# schematic.net
KiCad netlist of a schematic drawn in EAGLE
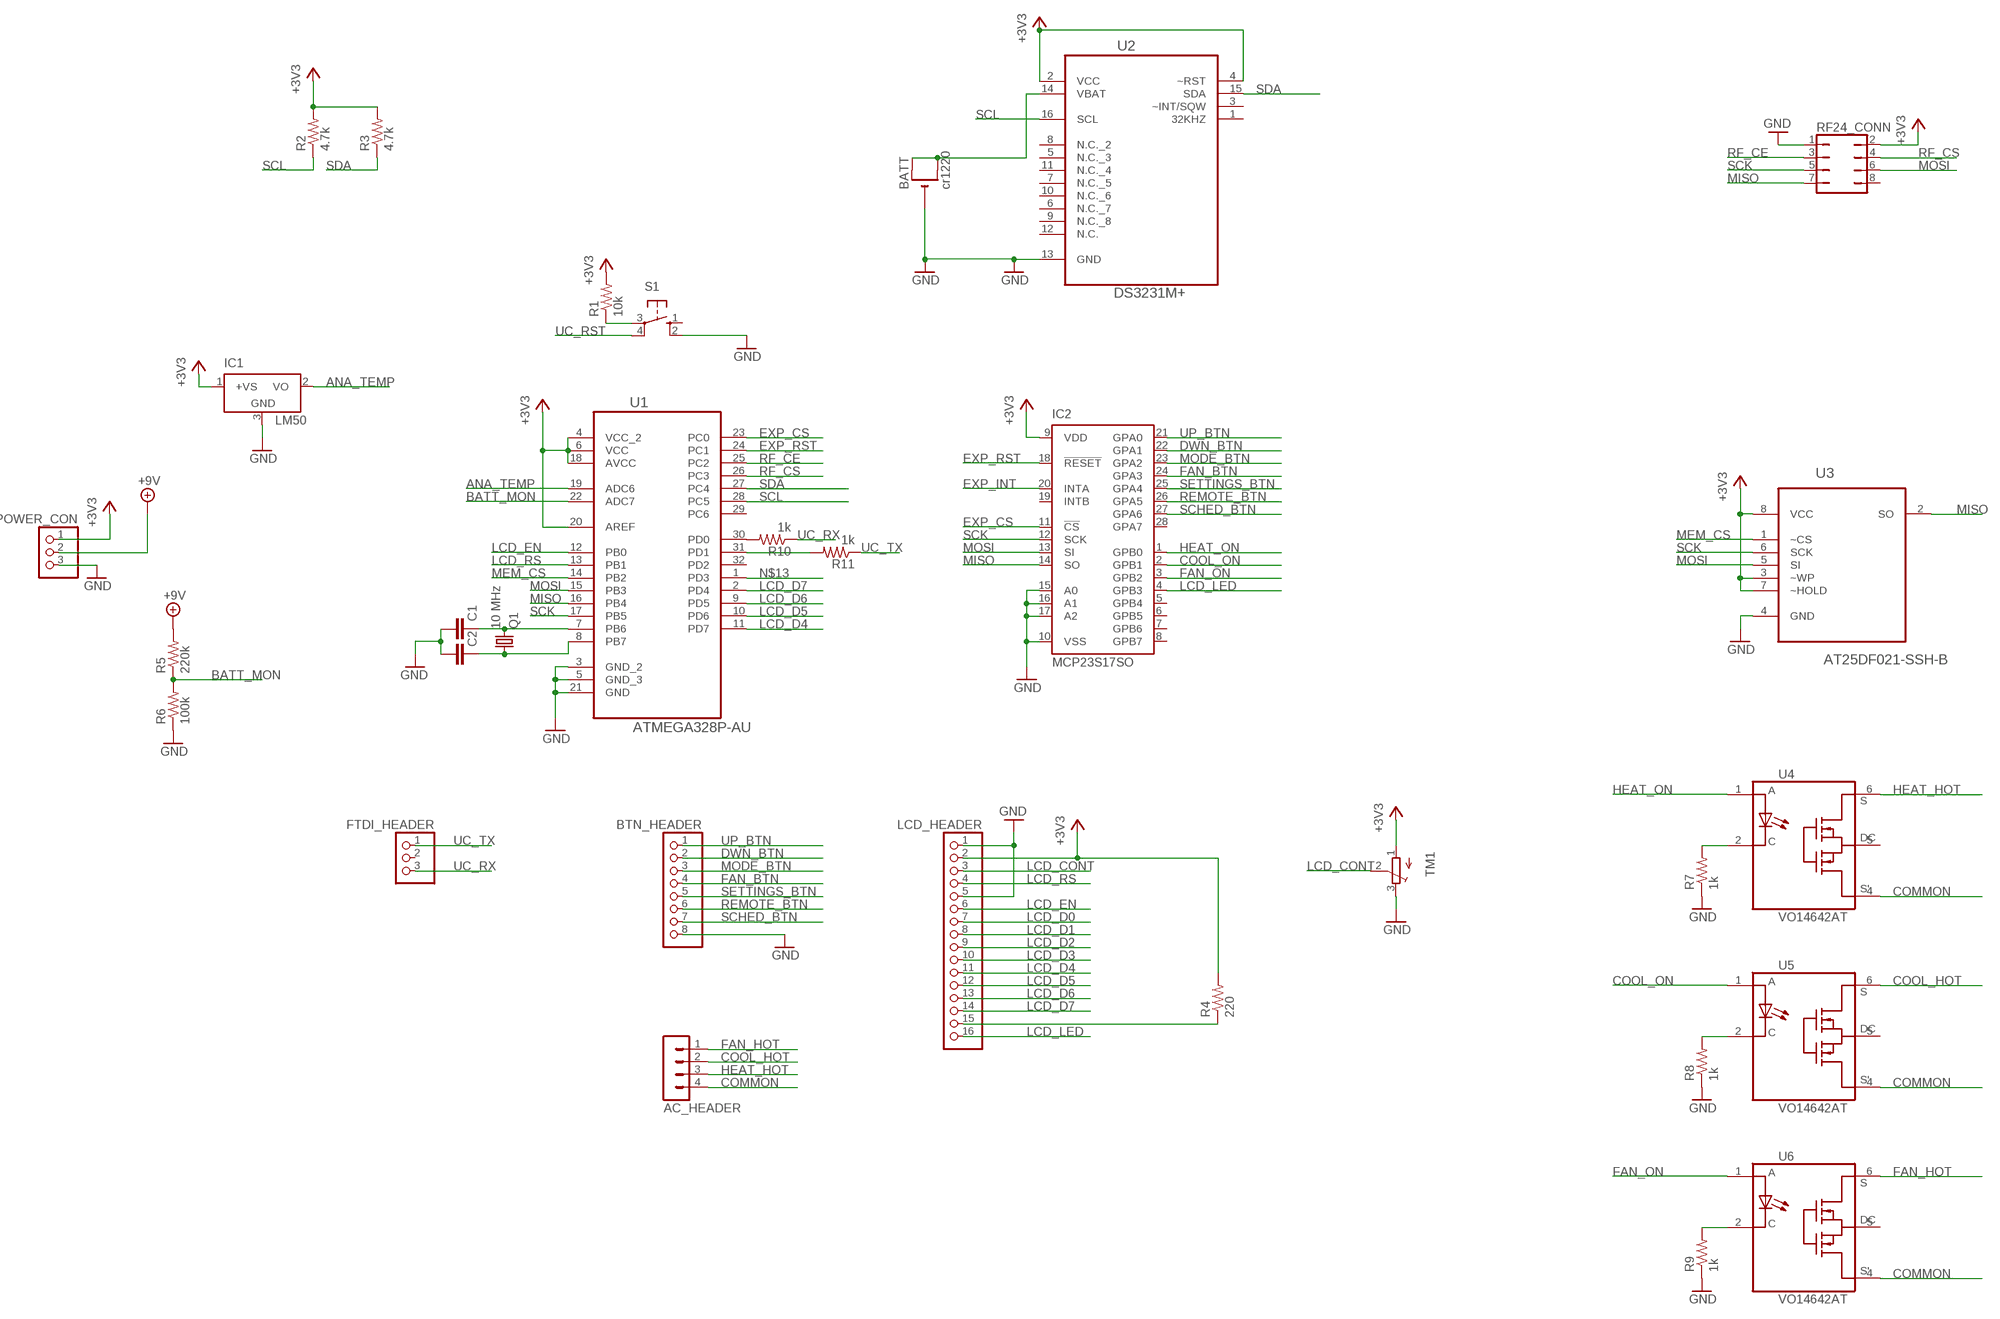
[diagram p0: schematic, sheet 1]

(export (version "E")
  (design (tool "Eeschema 10.0.6"))
  (components
    (comp (ref "AC_HEADER")
      (value "MA04-1")
      (footprint "eagle-import:MA04-1")
      (libsource (lib "eagle-import") (part "MA04-1"))
    )
    (comp (ref "BATT")
      (value "cr1220")
      (footprint "eagle-import:CR1220-SMD")
      (libsource (lib "eagle-import") (part "CR1220SMT"))
    )
    (comp (ref "BTN_HEADER")
      (value "PINHD-1X8BIG")
      (footprint "eagle-import:1X08-BIG")
      (libsource (lib "eagle-import") (part "PINHD-1X8BIG"))
    )
    (comp (ref "C1")
      (value "C-EUC0402")
      (footprint "eagle-import:C0402")
      (libsource (lib "eagle-import") (part "C-EUC0402"))
    )
    (comp (ref "C2")
      (value "C-EUC0402")
      (footprint "eagle-import:C0402")
      (libsource (lib "eagle-import") (part "C-EUC0402"))
    )
    (comp (ref "FTDI_HEADER")
      (value "PINHD-1X3")
      (footprint "eagle-import:1X03")
      (libsource (lib "eagle-import") (part "PINHD-1X3"))
    )
    (comp (ref "IC1")
      (value "LM50")
      (footprint "eagle-import:SOT23")
      (libsource (lib "eagle-import") (part "LM50"))
    )
    (comp (ref "IC2")
      (value "MCP23S17SO")
      (footprint "eagle-import:SO28W")
      (fields (field (name "MF") "MICROCHIP") (field (name "MPN") "MCP23S17-E/SO"))
      (libsource (lib "eagle-import") (part "MCP23S17SO"))
    )
    (comp (ref "LCD_HEADER")
      (value "PINHD-1X16")
      (footprint "eagle-import:1X16")
      (libsource (lib "eagle-import") (part "PINHD-1X16"))
    )
    (comp (ref "POWER_CON")
      (value "PINHD-1X3")
      (footprint "eagle-import:1X03")
      (libsource (lib "eagle-import") (part "PINHD-1X3"))
    )
    (comp (ref "Q1")
      (value "10 MHz")
      (footprint "eagle-import:FC-12M")
      (libsource (lib "eagle-import") (part "FC-12M"))
    )
    (comp (ref "R1")
      (value "10k")
      (footprint "eagle-import:R0402")
      (libsource (lib "eagle-import") (part "R-US_R0402"))
    )
    (comp (ref "R2")
      (value "4.7k")
      (footprint "eagle-import:R0402")
      (libsource (lib "eagle-import") (part "R-US_R0402"))
    )
    (comp (ref "R3")
      (value "4.7k")
      (footprint "eagle-import:R0402")
      (libsource (lib "eagle-import") (part "R-US_R0402"))
    )
    (comp (ref "R4")
      (value "220")
      (footprint "eagle-import:R0402")
      (libsource (lib "eagle-import") (part "R-US_R0402"))
    )
    (comp (ref "R5")
      (value "220k")
      (footprint "eagle-import:R0402")
      (libsource (lib "eagle-import") (part "R-US_R0402"))
    )
    (comp (ref "R6")
      (value "100k")
      (footprint "eagle-import:R0402")
      (libsource (lib "eagle-import") (part "R-US_R0402"))
    )
    (comp (ref "R7")
      (value "1k")
      (footprint "eagle-import:R0402")
      (libsource (lib "eagle-import") (part "R-US_R0402"))
    )
    (comp (ref "R8")
      (value "1k")
      (footprint "eagle-import:R0402")
      (libsource (lib "eagle-import") (part "R-US_R0402"))
    )
    (comp (ref "R9")
      (value "1k")
      (footprint "eagle-import:R0402")
      (libsource (lib "eagle-import") (part "R-US_R0402"))
    )
    (comp (ref "R10")
      (value "1k")
      (footprint "eagle-import:R0402")
      (libsource (lib "eagle-import") (part "R-US_R0402"))
    )
    (comp (ref "R11")
      (value "1k")
      (footprint "eagle-import:R0402")
      (libsource (lib "eagle-import") (part "R-US_R0402"))
    )
    (comp (ref "RF24_CONN")
      (value "JP4Q")
      (footprint "eagle-import:JP4Q")
      (libsource (lib "eagle-import") (part "JP4Q"))
    )
    (comp (ref "S1")
      (value "10-XX")
      (footprint "eagle-import:B3F-10XX")
      (fields (field (name "MPN") "B3F-1000"))
      (libsource (lib "eagle-import") (part "10-XX"))
    )
    (comp (ref "TM1")
      (value "TRIMPOTTC33X")
      (footprint "eagle-import:TC33X")
      (libsource (lib "eagle-import") (part "TRIMPOTTC33X"))
    )
    (comp (ref "U1")
      (value "ATMEGA328P-AU")
      (footprint "eagle-import:QFP80P900X900X120-32N")
      (libsource (lib "eagle-import") (part "ATMEGA328P-AU"))
    )
    (comp (ref "U2")
      (value "DS3231M+")
      (footprint "eagle-import:SOIC127P1032X265-16N")
      (libsource (lib "eagle-import") (part "DS3231M+"))
    )
    (comp (ref "U3")
      (value "AT25DF021-SSH-B")
      (footprint "eagle-import:SOIC127P600X175-8N")
      (libsource (lib "eagle-import") (part "AT25DF021-SSH-B"))
    )
    (comp (ref "U4")
      (value "VO14642AT")
      (footprint "eagle-import:DIP762W50P254L730H410Q6")
      (fields (field (name "DIGI-KEY_PART_NUMBER") "VO14642AT-ND") (field (name "MF") "Vishay"))
      (libsource (lib "eagle-import") (part "VO14642AT"))
    )
    (comp (ref "U5")
      (value "VO14642AT")
      (footprint "eagle-import:DIP762W50P254L730H410Q6")
      (fields (field (name "DIGI-KEY_PART_NUMBER") "VO14642AT-ND") (field (name "MF") "Vishay"))
      (libsource (lib "eagle-import") (part "VO14642AT"))
    )
    (comp (ref "U6")
      (value "VO14642AT")
      (footprint "eagle-import:DIP762W50P254L730H410Q6")
      (fields (field (name "DIGI-KEY_PART_NUMBER") "VO14642AT-ND") (field (name "MF") "Vishay"))
      (libsource (lib "eagle-import") (part "VO14642AT"))
    )
  )
  (nets
    (net (code "1") (name "+3V3") (class "Default")
      (node (ref "IC1") (pin "1") (pinfunction "+VS_1") (pintype "input"))
      (node (ref "IC2") (pin "9") (pinfunction "VDD_9") (pintype "power_in"))
      (node (ref "LCD_HEADER") (pin "2") (pinfunction "2_2") (pintype "passive"))
      (node (ref "POWER_CON") (pin "1") (pinfunction "1_1") (pintype "passive"))
      (node (ref "R1") (pin "2") (pinfunction "2_2") (pintype "passive"))
      (node (ref "R2") (pin "2") (pinfunction "2_2") (pintype "passive"))
      (node (ref "R3") (pin "2") (pinfunction "2_2") (pintype "passive"))
      (node (ref "R4") (pin "2") (pinfunction "2_2") (pintype "passive"))
      (node (ref "RF24_CONN") (pin "2") (pinfunction "2_2") (pintype "passive"))
      (node (ref "TM1") (pin "1") (pinfunction "A_1") (pintype "passive"))
      (node (ref "U1") (pin "18") (pinfunction "AVCC_18") (pintype "power_in"))
      (node (ref "U1") (pin "20") (pinfunction "AREF_20") (pintype "input"))
      (node (ref "U1") (pin "4") (pinfunction "VCC_2_4") (pintype "power_in"))
      (node (ref "U1") (pin "6") (pinfunction "VCC_6") (pintype "power_in"))
      (node (ref "U2") (pin "2") (pinfunction "VCC_2") (pintype "power_in"))
      (node (ref "U2") (pin "4") (pinfunction "~{RST}_4") (pintype "bidirectional"))
      (node (ref "U3") (pin "3") (pinfunction "~{WP}_3") (pintype "input"))
      (node (ref "U3") (pin "7") (pinfunction "~{HOLD}_7") (pintype "input"))
      (node (ref "U3") (pin "8") (pinfunction "VCC_8") (pintype "power_in"))
    )
    (net (code "2") (name "+9V") (class "Default")
      (node (ref "POWER_CON") (pin "2") (pinfunction "2_2") (pintype "passive"))
      (node (ref "R5") (pin "2") (pinfunction "2_2") (pintype "passive"))
    )
    (net (code "3") (name "/ANA_TEMP") (class "Default")
      (node (ref "IC1") (pin "2") (pinfunction "VO_2") (pintype "input"))
      (node (ref "U1") (pin "19") (pinfunction "ADC6_19") (pintype "input"))
    )
    (net (code "4") (name "/BATT_MON") (class "Default")
      (node (ref "R5") (pin "1") (pinfunction "1_1") (pintype "passive"))
      (node (ref "R6") (pin "2") (pinfunction "2_2") (pintype "passive"))
      (node (ref "U1") (pin "22") (pinfunction "ADC7_22") (pintype "input"))
    )
    (net (code "5") (name "/COMMON") (class "Default")
      (node (ref "AC_HEADER") (pin "4") (pinfunction "4_4") (pintype "passive"))
      (node (ref "U4") (pin "4") (pinfunction "S'_4") (pintype "passive"))
      (node (ref "U5") (pin "4") (pinfunction "S'_4") (pintype "passive"))
      (node (ref "U6") (pin "4") (pinfunction "S'_4") (pintype "passive"))
    )
    (net (code "6") (name "/COOL_HOT") (class "Default")
      (node (ref "AC_HEADER") (pin "2") (pinfunction "2_2") (pintype "passive"))
      (node (ref "U5") (pin "6") (pinfunction "S_6") (pintype "passive"))
    )
    (net (code "7") (name "/COOL_ON") (class "Default")
      (node (ref "IC2") (pin "2") (pinfunction "GPB1_2") (pintype "bidirectional"))
      (node (ref "U5") (pin "1") (pinfunction "A_1") (pintype "passive"))
    )
    (net (code "8") (name "/DWN_BTN") (class "Default")
      (node (ref "BTN_HEADER") (pin "2") (pinfunction "2_2") (pintype "passive"))
      (node (ref "IC2") (pin "22") (pinfunction "GPA1_22") (pintype "bidirectional"))
    )
    (net (code "9") (name "/EXP_CS") (class "Default")
      (node (ref "IC2") (pin "11") (pinfunction "~{CS}_11") (pintype "input"))
      (node (ref "U1") (pin "23") (pinfunction "PC0_23") (pintype "bidirectional"))
    )
    (net (code "10") (name "/EXP_INT") (class "Default")
      (node (ref "IC2") (pin "20") (pinfunction "INTA_20") (pintype "output"))
    )
    (net (code "11") (name "/EXP_RST") (class "Default")
      (node (ref "IC2") (pin "18") (pinfunction "~{RESET}_18") (pintype "input"))
      (node (ref "U1") (pin "24") (pinfunction "PC1_24") (pintype "bidirectional"))
    )
    (net (code "12") (name "/FAN_BTN") (class "Default")
      (node (ref "BTN_HEADER") (pin "4") (pinfunction "4_4") (pintype "passive"))
      (node (ref "IC2") (pin "24") (pinfunction "GPA3_24") (pintype "bidirectional"))
    )
    (net (code "13") (name "/FAN_HOT") (class "Default")
      (node (ref "AC_HEADER") (pin "1") (pinfunction "1_1") (pintype "passive"))
      (node (ref "U6") (pin "6") (pinfunction "S_6") (pintype "passive"))
    )
    (net (code "14") (name "/FAN_ON") (class "Default")
      (node (ref "IC2") (pin "3") (pinfunction "GPB2_3") (pintype "bidirectional"))
      (node (ref "U6") (pin "1") (pinfunction "A_1") (pintype "passive"))
    )
    (net (code "15") (name "/HEAT_HOT") (class "Default")
      (node (ref "AC_HEADER") (pin "3") (pinfunction "3_3") (pintype "passive"))
      (node (ref "U4") (pin "6") (pinfunction "S_6") (pintype "passive"))
    )
    (net (code "16") (name "/HEAT_ON") (class "Default")
      (node (ref "IC2") (pin "1") (pinfunction "GPB0_1") (pintype "bidirectional"))
      (node (ref "U4") (pin "1") (pinfunction "A_1") (pintype "passive"))
    )
    (net (code "17") (name "/LCD_CONT") (class "Default")
      (node (ref "LCD_HEADER") (pin "3") (pinfunction "3_3") (pintype "passive"))
      (node (ref "TM1") (pin "2") (pinfunction "S_2") (pintype "passive"))
    )
    (net (code "18") (name "/LCD_D0") (class "Default")
      (node (ref "LCD_HEADER") (pin "7") (pinfunction "7_7") (pintype "passive"))
    )
    (net (code "19") (name "/LCD_D1") (class "Default")
      (node (ref "LCD_HEADER") (pin "8") (pinfunction "8_8") (pintype "passive"))
    )
    (net (code "20") (name "/LCD_D2") (class "Default")
      (node (ref "LCD_HEADER") (pin "9") (pinfunction "9_9") (pintype "passive"))
    )
    (net (code "21") (name "/LCD_D3") (class "Default")
      (node (ref "LCD_HEADER") (pin "10") (pinfunction "10_10") (pintype "passive"))
    )
    (net (code "22") (name "/LCD_D4") (class "Default")
      (node (ref "LCD_HEADER") (pin "11") (pinfunction "11_11") (pintype "passive"))
      (node (ref "U1") (pin "11") (pinfunction "PD7_11") (pintype "bidirectional"))
    )
    (net (code "23") (name "/LCD_D5") (class "Default")
      (node (ref "LCD_HEADER") (pin "12") (pinfunction "12_12") (pintype "passive"))
      (node (ref "U1") (pin "10") (pinfunction "PD6_10") (pintype "bidirectional"))
    )
    (net (code "24") (name "/LCD_D6") (class "Default")
      (node (ref "LCD_HEADER") (pin "13") (pinfunction "13_13") (pintype "passive"))
      (node (ref "U1") (pin "9") (pinfunction "PD5_9") (pintype "bidirectional"))
    )
    (net (code "25") (name "/LCD_D7") (class "Default")
      (node (ref "LCD_HEADER") (pin "14") (pinfunction "14_14") (pintype "passive"))
      (node (ref "U1") (pin "2") (pinfunction "PD4_2") (pintype "bidirectional"))
    )
    (net (code "26") (name "/LCD_EN") (class "Default")
      (node (ref "LCD_HEADER") (pin "6") (pinfunction "6_6") (pintype "passive"))
      (node (ref "U1") (pin "12") (pinfunction "PB0_12") (pintype "bidirectional"))
    )
    (net (code "27") (name "/LCD_LED") (class "Default")
      (node (ref "IC2") (pin "4") (pinfunction "GPB3_4") (pintype "bidirectional"))
      (node (ref "LCD_HEADER") (pin "16") (pinfunction "16_16") (pintype "passive"))
    )
    (net (code "28") (name "/LCD_RS") (class "Default")
      (node (ref "LCD_HEADER") (pin "4") (pinfunction "4_4") (pintype "passive"))
      (node (ref "U1") (pin "13") (pinfunction "PB1_13") (pintype "bidirectional"))
    )
    (net (code "29") (name "/MEM_CS") (class "Default")
      (node (ref "U1") (pin "14") (pinfunction "PB2_14") (pintype "bidirectional"))
      (node (ref "U3") (pin "1") (pinfunction "~{CS}_1") (pintype "input"))
    )
    (net (code "30") (name "/MISO") (class "Default")
      (node (ref "IC2") (pin "14") (pinfunction "SO_14") (pintype "output"))
      (node (ref "RF24_CONN") (pin "7") (pinfunction "7_7") (pintype "passive"))
      (node (ref "U1") (pin "16") (pinfunction "PB4_16") (pintype "bidirectional"))
      (node (ref "U3") (pin "2") (pinfunction "SO_2") (pintype "output"))
    )
    (net (code "31") (name "/MODE_BTN") (class "Default")
      (node (ref "BTN_HEADER") (pin "3") (pinfunction "3_3") (pintype "passive"))
      (node (ref "IC2") (pin "23") (pinfunction "GPA2_23") (pintype "bidirectional"))
    )
    (net (code "32") (name "/MOSI") (class "Default")
      (node (ref "IC2") (pin "13") (pinfunction "SI_13") (pintype "input"))
      (node (ref "RF24_CONN") (pin "6") (pinfunction "6_6") (pintype "passive"))
      (node (ref "U1") (pin "15") (pinfunction "PB3_15") (pintype "bidirectional"))
      (node (ref "U3") (pin "5") (pinfunction "SI_5") (pintype "input"))
    )
    (net (code "33") (name "/N$13") (class "Default")
      (node (ref "U1") (pin "1") (pinfunction "PD3_1") (pintype "bidirectional"))
    )
    (net (code "34") (name "/REMOTE_BTN") (class "Default")
      (node (ref "BTN_HEADER") (pin "6") (pinfunction "6_6") (pintype "passive"))
      (node (ref "IC2") (pin "26") (pinfunction "GPA5_26") (pintype "bidirectional"))
    )
    (net (code "35") (name "/RF_CE") (class "Default")
      (node (ref "RF24_CONN") (pin "3") (pinfunction "3_3") (pintype "passive"))
      (node (ref "U1") (pin "25") (pinfunction "PC2_25") (pintype "bidirectional"))
    )
    (net (code "36") (name "/RF_CS") (class "Default")
      (node (ref "RF24_CONN") (pin "4") (pinfunction "4_4") (pintype "passive"))
      (node (ref "U1") (pin "26") (pinfunction "PC3_26") (pintype "bidirectional"))
    )
    (net (code "37") (name "/SCHED_BTN") (class "Default")
      (node (ref "BTN_HEADER") (pin "7") (pinfunction "7_7") (pintype "passive"))
      (node (ref "IC2") (pin "27") (pinfunction "GPA6_27") (pintype "bidirectional"))
    )
    (net (code "38") (name "/SCK") (class "Default")
      (node (ref "IC2") (pin "12") (pinfunction "SCK_12") (pintype "input"))
      (node (ref "RF24_CONN") (pin "5") (pinfunction "5_5") (pintype "passive"))
      (node (ref "U1") (pin "17") (pinfunction "PB5_17") (pintype "bidirectional"))
      (node (ref "U3") (pin "6") (pinfunction "SCK_6") (pintype "input"))
    )
    (net (code "39") (name "/SCL") (class "Default")
      (node (ref "R2") (pin "1") (pinfunction "1_1") (pintype "passive"))
      (node (ref "U1") (pin "28") (pinfunction "PC5_28") (pintype "bidirectional"))
      (node (ref "U2") (pin "16") (pinfunction "SCL_16") (pintype "input"))
    )
    (net (code "40") (name "/SDA") (class "Default")
      (node (ref "R3") (pin "1") (pinfunction "1_1") (pintype "passive"))
      (node (ref "U1") (pin "27") (pinfunction "PC4_27") (pintype "bidirectional"))
      (node (ref "U2") (pin "15") (pinfunction "SDA_15") (pintype "bidirectional"))
    )
    (net (code "41") (name "/SETTINGS_BTN") (class "Default")
      (node (ref "BTN_HEADER") (pin "5") (pinfunction "5_5") (pintype "passive"))
      (node (ref "IC2") (pin "25") (pinfunction "GPA4_25") (pintype "bidirectional"))
    )
    (net (code "42") (name "/UC_RST") (class "Default")
      (node (ref "S1") (pin "4") (pinfunction "P1_4") (pintype "passive"))
    )
    (net (code "43") (name "/UC_RX") (class "Default")
      (node (ref "FTDI_HEADER") (pin "3") (pinfunction "3_3") (pintype "passive"))
      (node (ref "R10") (pin "1") (pinfunction "1_1") (pintype "passive"))
    )
    (net (code "44") (name "/UC_TX") (class "Default")
      (node (ref "FTDI_HEADER") (pin "1") (pinfunction "1_1") (pintype "passive"))
      (node (ref "R11") (pin "1") (pinfunction "1_1") (pintype "passive"))
    )
    (net (code "45") (name "/UP_BTN") (class "Default")
      (node (ref "BTN_HEADER") (pin "1") (pinfunction "1_1") (pintype "passive"))
      (node (ref "IC2") (pin "21") (pinfunction "GPA0_21") (pintype "bidirectional"))
    )
    (net (code "46") (name "GND") (class "Default")
      (node (ref "BATT") (pin "-") (pinfunction "-_-") (pintype "passive"))
      (node (ref "BTN_HEADER") (pin "8") (pinfunction "8_8") (pintype "passive"))
      (node (ref "C1") (pin "2") (pinfunction "2_2") (pintype "passive"))
      (node (ref "C2") (pin "2") (pinfunction "2_2") (pintype "passive"))
      (node (ref "IC1") (pin "3") (pinfunction "GND_3") (pintype "power_in"))
      (node (ref "IC2") (pin "10") (pinfunction "VSS_10") (pintype "power_in"))
      (node (ref "IC2") (pin "15") (pinfunction "A0_15") (pintype "input"))
      (node (ref "IC2") (pin "16") (pinfunction "A1_16") (pintype "input"))
      (node (ref "IC2") (pin "17") (pinfunction "A2_17") (pintype "input"))
      (node (ref "LCD_HEADER") (pin "1") (pinfunction "1_1") (pintype "passive"))
      (node (ref "LCD_HEADER") (pin "5") (pinfunction "5_5") (pintype "passive"))
      (node (ref "POWER_CON") (pin "3") (pinfunction "3_3") (pintype "passive"))
      (node (ref "R6") (pin "1") (pinfunction "1_1") (pintype "passive"))
      (node (ref "R7") (pin "1") (pinfunction "1_1") (pintype "passive"))
      (node (ref "R8") (pin "1") (pinfunction "1_1") (pintype "passive"))
      (node (ref "R9") (pin "1") (pinfunction "1_1") (pintype "passive"))
      (node (ref "RF24_CONN") (pin "1") (pinfunction "1_1") (pintype "passive"))
      (node (ref "S1") (pin "2") (pinfunction "S1_2") (pintype "passive"))
      (node (ref "TM1") (pin "3") (pinfunction "E_3") (pintype "passive"))
      (node (ref "U1") (pin "21") (pinfunction "GND_21") (pintype "passive"))
      (node (ref "U1") (pin "3") (pinfunction "GND_2_3") (pintype "passive"))
      (node (ref "U1") (pin "5") (pinfunction "GND_3_5") (pintype "passive"))
      (node (ref "U2") (pin "13") (pinfunction "GND_13") (pintype "passive"))
      (node (ref "U3") (pin "4") (pinfunction "GND_4") (pintype "passive"))
    )
    (net (code "47") (name "Net-(BATT-+)") (class "Default")
      (node (ref "BATT") (pin "+$1") (pinfunction "+_+$1") (pintype "passive"))
      (node (ref "BATT") (pin "+$2") (pinfunction "+1_+$2") (pintype "passive"))
      (node (ref "U2") (pin "14") (pinfunction "VBAT_14") (pintype "power_in"))
    )
    (net (code "48") (name "Net-(LCD_HEADER-Pad15)") (class "Default")
      (node (ref "LCD_HEADER") (pin "15") (pinfunction "15_15") (pintype "passive"))
      (node (ref "R4") (pin "1") (pinfunction "1_1") (pintype "passive"))
    )
    (net (code "49") (name "Net-(S1-P)") (class "Default")
      (node (ref "R1") (pin "1") (pinfunction "1_1") (pintype "passive"))
      (node (ref "S1") (pin "3") (pinfunction "P_3") (pintype "passive"))
    )
    (net (code "50") (name "Net-(U1-PB6)") (class "Default")
      (node (ref "C1") (pin "1") (pinfunction "1_1") (pintype "passive"))
      (node (ref "Q1") (pin "2") (pinfunction "2_2") (pintype "passive"))
      (node (ref "U1") (pin "7") (pinfunction "PB6_7") (pintype "bidirectional"))
    )
    (net (code "51") (name "Net-(U1-PB7)") (class "Default")
      (node (ref "C2") (pin "1") (pinfunction "1_1") (pintype "passive"))
      (node (ref "Q1") (pin "1") (pinfunction "1_1") (pintype "passive"))
      (node (ref "U1") (pin "8") (pinfunction "PB7_8") (pintype "bidirectional"))
    )
    (net (code "52") (name "Net-(U1-PD0)") (class "Default")
      (node (ref "R10") (pin "2") (pinfunction "2_2") (pintype "passive"))
      (node (ref "U1") (pin "30") (pinfunction "PD0_30") (pintype "bidirectional"))
    )
    (net (code "53") (name "Net-(U1-PD1)") (class "Default")
      (node (ref "R11") (pin "2") (pinfunction "2_2") (pintype "passive"))
      (node (ref "U1") (pin "31") (pinfunction "PD1_31") (pintype "bidirectional"))
    )
    (net (code "54") (name "Net-(U4-C)") (class "Default")
      (node (ref "R7") (pin "2") (pinfunction "2_2") (pintype "passive"))
      (node (ref "U4") (pin "2") (pinfunction "C_2") (pintype "passive"))
    )
    (net (code "55") (name "Net-(U5-C)") (class "Default")
      (node (ref "R8") (pin "2") (pinfunction "2_2") (pintype "passive"))
      (node (ref "U5") (pin "2") (pinfunction "C_2") (pintype "passive"))
    )
    (net (code "56") (name "Net-(U6-C)") (class "Default")
      (node (ref "R9") (pin "2") (pinfunction "2_2") (pintype "passive"))
      (node (ref "U6") (pin "2") (pinfunction "C_2") (pintype "passive"))
    )
    (net (code "57") (name "unconnected-(FTDI_HEADER-Pad2)") (class "Default")
      (node (ref "FTDI_HEADER") (pin "2") (pinfunction "2_2") (pintype "passive"))
    )
    (net (code "58") (name "unconnected-(IC2-GPA7-Pad28)") (class "Default")
      (node (ref "IC2") (pin "28") (pinfunction "GPA7_28") (pintype "bidirectional"))
    )
    (net (code "59") (name "unconnected-(IC2-GPB4-Pad5)") (class "Default")
      (node (ref "IC2") (pin "5") (pinfunction "GPB4_5") (pintype "bidirectional"))
    )
    (net (code "60") (name "unconnected-(IC2-GPB5-Pad6)") (class "Default")
      (node (ref "IC2") (pin "6") (pinfunction "GPB5_6") (pintype "bidirectional"))
    )
    (net (code "61") (name "unconnected-(IC2-GPB6-Pad7)") (class "Default")
      (node (ref "IC2") (pin "7") (pinfunction "GPB6_7") (pintype "bidirectional"))
    )
    (net (code "62") (name "unconnected-(IC2-GPB7-Pad8)") (class "Default")
      (node (ref "IC2") (pin "8") (pinfunction "GPB7_8") (pintype "bidirectional"))
    )
    (net (code "63") (name "unconnected-(IC2-INTB-Pad19)") (class "Default")
      (node (ref "IC2") (pin "19") (pinfunction "INTB_19") (pintype "output"))
    )
    (net (code "64") (name "unconnected-(RF24_CONN-Pad8)") (class "Default")
      (node (ref "RF24_CONN") (pin "8") (pinfunction "8_8") (pintype "passive"))
    )
    (net (code "65") (name "unconnected-(S1-S-Pad1)") (class "Default")
      (node (ref "S1") (pin "1") (pinfunction "S_1") (pintype "passive"))
    )
    (net (code "66") (name "unconnected-(U1-PC6-Pad29)") (class "Default")
      (node (ref "U1") (pin "29") (pinfunction "PC6_29") (pintype "bidirectional"))
    )
    (net (code "67") (name "unconnected-(U1-PD2-Pad32)") (class "Default")
      (node (ref "U1") (pin "32") (pinfunction "PD2_32") (pintype "bidirectional"))
    )
    (net (code "68") (name "unconnected-(U2-32KHZ-Pad1)") (class "Default")
      (node (ref "U2") (pin "1") (pinfunction "32KHZ_1") (pintype "output"))
    )
    (net (code "69") (name "unconnected-(U2-N.C.-Pad12)") (class "Default")
      (node (ref "U2") (pin "12") (pinfunction "N.C._12") (pintype "no_connect"))
    )
    (net (code "70") (name "unconnected-(U2-N.C._2-Pad8)") (class "Default")
      (node (ref "U2") (pin "8") (pinfunction "N.C._2_8") (pintype "no_connect"))
    )
    (net (code "71") (name "unconnected-(U2-N.C._3-Pad5)") (class "Default")
      (node (ref "U2") (pin "5") (pinfunction "N.C._3_5") (pintype "no_connect"))
    )
    (net (code "72") (name "unconnected-(U2-N.C._4-Pad11)") (class "Default")
      (node (ref "U2") (pin "11") (pinfunction "N.C._4_11") (pintype "no_connect"))
    )
    (net (code "73") (name "unconnected-(U2-N.C._5-Pad7)") (class "Default")
      (node (ref "U2") (pin "7") (pinfunction "N.C._5_7") (pintype "no_connect"))
    )
    (net (code "74") (name "unconnected-(U2-N.C._6-Pad10)") (class "Default")
      (node (ref "U2") (pin "10") (pinfunction "N.C._6_10") (pintype "no_connect"))
    )
    (net (code "75") (name "unconnected-(U2-N.C._7-Pad6)") (class "Default")
      (node (ref "U2") (pin "6") (pinfunction "N.C._7_6") (pintype "no_connect"))
    )
    (net (code "76") (name "unconnected-(U2-N.C._8-Pad9)") (class "Default")
      (node (ref "U2") (pin "9") (pinfunction "N.C._8_9") (pintype "no_connect"))
    )
    (net (code "77") (name "unconnected-(U2-~{INT{slash}SQW}-Pad3)") (class "Default")
      (node (ref "U2") (pin "3") (pinfunction "~{INT/SQW}_3") (pintype "output"))
    )
    (net (code "78") (name "unconnected-(U4-DC-Pad5)") (class "Default")
      (node (ref "U4") (pin "5") (pinfunction "DC_5") (pintype "passive"))
    )
    (net (code "79") (name "unconnected-(U5-DC-Pad5)") (class "Default")
      (node (ref "U5") (pin "5") (pinfunction "DC_5") (pintype "passive"))
    )
    (net (code "80") (name "unconnected-(U6-DC-Pad5)") (class "Default")
      (node (ref "U6") (pin "5") (pinfunction "DC_5") (pintype "passive"))
    )
  )
)
